# 780-00036_rev3_Sch_Crate_Slot_Power_Inte.net
KiCad netlist of a schematic drawn in Altium Designer
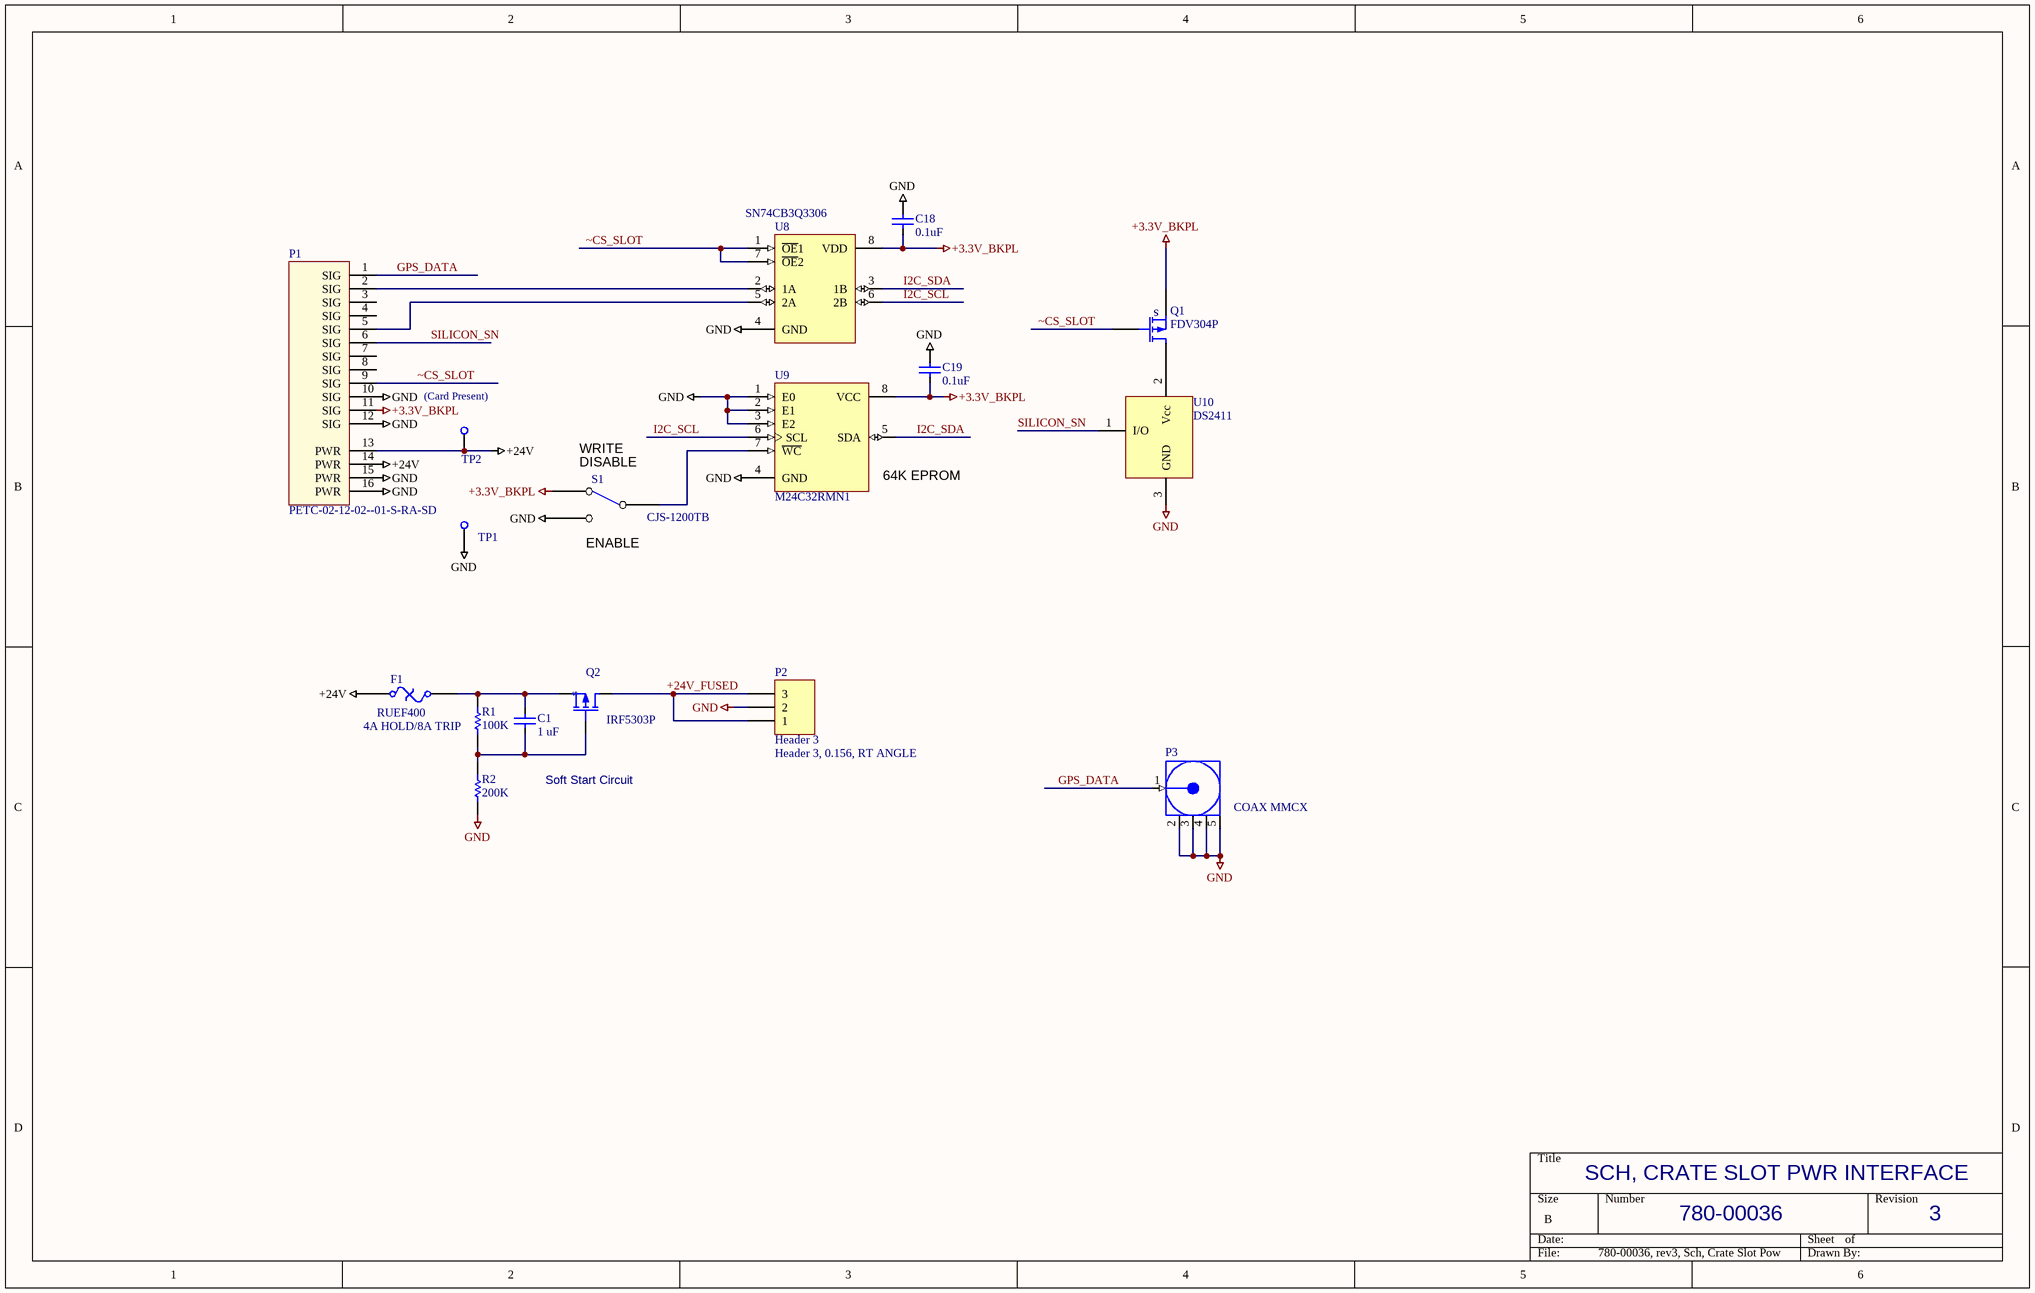
[diagram p0: 780-00036, rev3, Sch, Crate Slot Power Interface.SchDoc]

(export (version "E")
  (design (tool "Eeschema 10.0.6"))
  (components
    (comp (ref "C1")
      (value "1 uF")
      (footprint "SMD_0805")
      (description "Capacitor")
      (fields (field (name "Comment") "Cap SMD"))
      (libsource (lib "Richs Schematic Components") (part "Cap SMD"))
    )
    (comp (ref "C18")
      (value "0.1uF")
      (footprint "SMD_0805")
      (description "Capacitor")
      (fields (field (name "MANUFACTURER") "AVX") (field (name "Comment") "Cap SMD"))
      (libsource (lib "Richs Schematic Components") (part "Cap SMD"))
    )
    (comp (ref "C19")
      (value "0.1uF")
      (footprint "SMD_0805")
      (description "Capacitor")
      (fields (field (name "MANUFACTURER") "AVX") (field (name "Comment") "Cap SMD"))
      (libsource (lib "Richs Schematic Components") (part "Cap SMD"))
    )
    (comp (ref "F1")
      (value "RUEF400")
      (footprint "PolySwitch Radial 0.2")
      (description "PolySwitch RUE Series")
      (fields
        (field (name "MANUFACTURER") "Tyco Electronics")
        (field (name "ALTIUM_VALUE") "4A HOLD/8A TRIP")
      )
      (libsource (lib "Richs Schematic Components") (part "Fuse Thermal"))
    )
    (comp (ref "P1")
      (value "PETC-02-12-02--01-S-RA-SD")
      (footprint "PETC-02-12-02-01-RA")
      (description "SAMTEC, SIGNAL(12)+PWR(4)")
      (fields (field (name "MANUFACTURER") "SAMTEC"))
      (libsource (lib "Richs Schematic Components") (part "PETC-02-12-02--01-S-RA-SD"))
    )
    (comp (ref "P2")
      (value "Header 3")
      (footprint "HDR 1X3 0.156\" - RT ANGLE")
      (description "Header, 3-Pin, 0.156, RT ANGLE")
      (fields
        (field (name "MANUFACTURER") "TE Connectivity")
        (field (name "ALTIUM_VALUE") "Header 3, 0.156, RT ANGLE")
      )
      (libsource (lib "Richs Schematic Components") (part "Header 3, 0.156 RT ANGLE"))
    )
    (comp (ref "P3")
      (value "COAX MMCX")
      (footprint "Miscellaneous Connectors:MMCX2.54-V5")
      (description "RF Coaxial PCB Connector, MMCX; Thru-Hole, Vertical Mount Plug,  50 Ohm Impedance")
      (fields (field (name "MANUFACTURER") "Emerson"))
      (libsource (lib "Richs Schematic Components") (part "COAX-M"))
    )
    (comp (ref "Q1")
      (value "FDV304P")
      (footprint "SMD_SOT23_3")
      (description "P-MOSFET LOGIC LEVEL")
      (fields (field (name "MANUFACTURER") "Fairchild"))
      (libsource (lib "Richs Schematic Components") (part "FDV304P"))
    )
    (comp (ref "Q2")
      (value "IRF5303P")
      (footprint "TO-252(D-PAK)  PowerPAD")
      (description "P-Chan MOSFET")
      (fields (field (name "MANUFACTURER") "INT'l Rectifier"))
      (libsource (lib "Richs Schematic Components") (part "IRF5303P"))
    )
    (comp (ref "R1")
      (value "100K")
      (footprint "SMD_0805")
      (description "Resistor 0805")
      (fields (field (name "MANUFACTURER") "Vishay/Dale") (field (name "Comment") "Res 0805"))
      (libsource (lib "Richs Schematic Components") (part "Res SMD"))
    )
    (comp (ref "R2")
      (value "200K")
      (footprint "SMD_0805")
      (description "Resistor 0805")
      (fields (field (name "MANUFACTURER") "Vishay/Dale") (field (name "Comment") "Res 0805"))
      (libsource (lib "Richs Schematic Components") (part "Res SMD"))
    )
    (comp (ref "S1")
      (value "CJS-1200TB")
      (footprint "CAS-120B")
      (fields (field (name "MANUFACTURER") "Copal Electronics"))
      (libsource (lib "JON_1_Library") (part "SW_SPDT_DOUG"))
    )
    (comp (ref "TP1")
      (value "Test Point SMD")
      (footprint "SMD_TEST POINT")
      (description "SMD loop test point")
      (libsource (lib "Richs Schematic Components") (part "Test Point SMD"))
    )
    (comp (ref "TP2")
      (value "Test Point SMD")
      (footprint "SMD_TEST POINT")
      (description "SMD loop test point")
      (libsource (lib "Richs Schematic Components") (part "Test Point SMD"))
    )
    (comp (ref "U8")
      (value "SN74CB3Q3306")
      (footprint "PW008_N")
      (description "Dual FET Bus Switch")
      (fields (field (name "MANUFACTURER") "TI") (field (name "Comment") "SN74CBT3306PWLE"))
      (libsource (lib "TI Logic Switch") (part "SN74CBT3306PWLE"))
    )
    (comp (ref "U9")
      (value "M24C32RMN1")
      (footprint "SOP8_N")
      (description "32 Kbit Serial I²C Bus EEPROM")
      (libsource (lib "ST Memory EEPROM Serial") (part "M24C32RMN1"))
    )
    (comp (ref "U10")
      (value "DS2411")
      (footprint "SMD_SOT23_3")
      (description "Silicon Serial Number")
      (fields (field (name "MANUFACTURER") "MAXIM"))
      (libsource (lib "Richs Schematic Components") (part "DS2411"))
    )
  )
  (nets
    (net (code "1") (name "+3.3V_BKPL") (class "Default")
      (node (ref "C18") (pin "1") (pinfunction "1_1") (pintype "passive"))
      (node (ref "C19") (pin "1") (pinfunction "1_1") (pintype "passive"))
      (node (ref "P1") (pin "11") (pinfunction "SIG_11") (pintype "passive"))
      (node (ref "Q1") (pin "2") (pinfunction "S_2") (pintype "passive"))
      (node (ref "S1") (pin "3") (pinfunction "NC_3") (pintype "passive"))
      (node (ref "U8") (pin "8") (pinfunction "VDD_8") (pintype "power_in"))
      (node (ref "U9") (pin "8") (pinfunction "VCC_8") (pintype "power_in"))
    )
    (net (code "2") (name "+24V") (class "Default")
      (node (ref "F1") (pin "1") (pinfunction "1_1") (pintype "passive"))
      (node (ref "P1") (pin "13") (pinfunction "PWR_13") (pintype "passive"))
      (node (ref "P1") (pin "14") (pinfunction "PWR_14") (pintype "passive"))
      (node (ref "TP2") (pin "1") (pinfunction "TP_1") (pintype "passive"))
    )
    (net (code "3") (name "/+24V_FUSED") (class "Default")
      (node (ref "P2") (pin "1") (pinfunction "1_1") (pintype "passive"))
      (node (ref "P2") (pin "3") (pinfunction "3_3") (pintype "passive"))
      (node (ref "Q2") (pin "2") (pinfunction "D_2") (pintype "passive"))
    )
    (net (code "4") (name "/GPS_DATA") (class "Default")
      (node (ref "P1") (pin "1") (pinfunction "SIG_1") (pintype "passive"))
      (node (ref "P3") (pin "1") (pinfunction "Signal_1") (pintype "input"))
    )
    (net (code "5") (name "/I2C_SCL") (class "Default")
      (node (ref "U8") (pin "6") (pinfunction "2B_6") (pintype "bidirectional"))
      (node (ref "U9") (pin "6") (pinfunction "SCL_6") (pintype "input"))
    )
    (net (code "6") (name "/I2C_SDA") (class "Default")
      (node (ref "U8") (pin "3") (pinfunction "1B_3") (pintype "bidirectional"))
      (node (ref "U9") (pin "5") (pinfunction "SDA_5") (pintype "bidirectional"))
    )
    (net (code "7") (name "/SILICON_SN") (class "Default")
      (node (ref "P1") (pin "6") (pinfunction "SIG_6") (pintype "passive"))
      (node (ref "U10") (pin "1") (pinfunction "I/O_1") (pintype "passive"))
    )
    (net (code "8") (name "/~CS_SLOT") (class "Default")
      (node (ref "P1") (pin "9") (pinfunction "SIG_9") (pintype "passive"))
      (node (ref "Q1") (pin "1") (pinfunction "G_1") (pintype "passive"))
      (node (ref "U8") (pin "1") (pinfunction "~{OE}1_1") (pintype "input"))
      (node (ref "U8") (pin "7") (pinfunction "~{OE}2_7") (pintype "input"))
    )
    (net (code "9") (name "GND") (class "Default")
      (node (ref "C18") (pin "2") (pinfunction "2_2") (pintype "passive"))
      (node (ref "C19") (pin "2") (pinfunction "2_2") (pintype "passive"))
      (node (ref "P1") (pin "10") (pinfunction "SIG_10") (pintype "passive"))
      (node (ref "P1") (pin "12") (pinfunction "SIG_12") (pintype "passive"))
      (node (ref "P1") (pin "15") (pinfunction "PWR_15") (pintype "passive"))
      (node (ref "P1") (pin "16") (pinfunction "PWR_16") (pintype "passive"))
      (node (ref "P2") (pin "2") (pinfunction "2_2") (pintype "passive"))
      (node (ref "P3") (pin "2") (pinfunction "GND_2") (pintype "power_in"))
      (node (ref "P3") (pin "3") (pinfunction "GND_3") (pintype "power_in"))
      (node (ref "P3") (pin "4") (pinfunction "GND_4") (pintype "power_in"))
      (node (ref "P3") (pin "5") (pinfunction "GND_5") (pintype "power_in"))
      (node (ref "R2") (pin "1") (pinfunction "1_1") (pintype "passive"))
      (node (ref "S1") (pin "1") (pinfunction "NO_1") (pintype "passive"))
      (node (ref "TP1") (pin "1") (pinfunction "TP_1") (pintype "passive"))
      (node (ref "U10") (pin "3") (pinfunction "GND_3") (pintype "passive"))
      (node (ref "U8") (pin "4") (pinfunction "GND_4") (pintype "power_in"))
      (node (ref "U9") (pin "1") (pinfunction "E0_1") (pintype "input"))
      (node (ref "U9") (pin "2") (pinfunction "E1_2") (pintype "input"))
      (node (ref "U9") (pin "3") (pinfunction "E2_3") (pintype "input"))
      (node (ref "U9") (pin "4") (pinfunction "GND_4") (pintype "power_in"))
    )
    (net (code "10") (name "Net-(Q1-D)") (class "Default")
      (node (ref "Q1") (pin "3") (pinfunction "D_3") (pintype "passive"))
      (node (ref "U10") (pin "2") (pinfunction "Vcc_2") (pintype "passive"))
    )
    (net (code "11") (name "Net-(Q2-G)") (class "Default")
      (node (ref "C1") (pin "1") (pinfunction "1_1") (pintype "passive"))
      (node (ref "Q2") (pin "1") (pinfunction "G_1") (pintype "passive"))
      (node (ref "R1") (pin "1") (pinfunction "1_1") (pintype "passive"))
      (node (ref "R2") (pin "2") (pinfunction "2_2") (pintype "passive"))
    )
    (net (code "12") (name "Net-(Q2-S)") (class "Default")
      (node (ref "C1") (pin "2") (pinfunction "2_2") (pintype "passive"))
      (node (ref "F1") (pin "2") (pinfunction "2_2") (pintype "passive"))
      (node (ref "Q2") (pin "3") (pinfunction "S_3") (pintype "passive"))
      (node (ref "R1") (pin "2") (pinfunction "2_2") (pintype "passive"))
    )
    (net (code "13") (name "Net-(S1-COM)") (class "Default")
      (node (ref "S1") (pin "2") (pinfunction "COM_2") (pintype "passive"))
      (node (ref "U9") (pin "7") (pinfunction "~{WC}_7") (pintype "input"))
    )
    (net (code "14") (name "Net-(U8-1A)") (class "Default")
      (node (ref "P1") (pin "2") (pinfunction "SIG_2") (pintype "passive"))
      (node (ref "U8") (pin "2") (pinfunction "1A_2") (pintype "bidirectional"))
    )
    (net (code "15") (name "Net-(U8-2A)") (class "Default")
      (node (ref "P1") (pin "5") (pinfunction "SIG_5") (pintype "passive"))
      (node (ref "U8") (pin "5") (pinfunction "2A_5") (pintype "bidirectional"))
    )
    (net (code "16") (name "unconnected-(P1-SIG-Pad3)") (class "Default")
      (node (ref "P1") (pin "3") (pinfunction "SIG_3") (pintype "passive"))
    )
    (net (code "17") (name "unconnected-(P1-SIG-Pad4)") (class "Default")
      (node (ref "P1") (pin "4") (pinfunction "SIG_4") (pintype "passive"))
    )
    (net (code "18") (name "unconnected-(P1-SIG-Pad7)") (class "Default")
      (node (ref "P1") (pin "7") (pinfunction "SIG_7") (pintype "passive"))
    )
    (net (code "19") (name "unconnected-(P1-SIG-Pad8)") (class "Default")
      (node (ref "P1") (pin "8") (pinfunction "SIG_8") (pintype "passive"))
    )
  )
)
